# mainboard.net
KiCad netlist of a schematic drawn in EAGLE
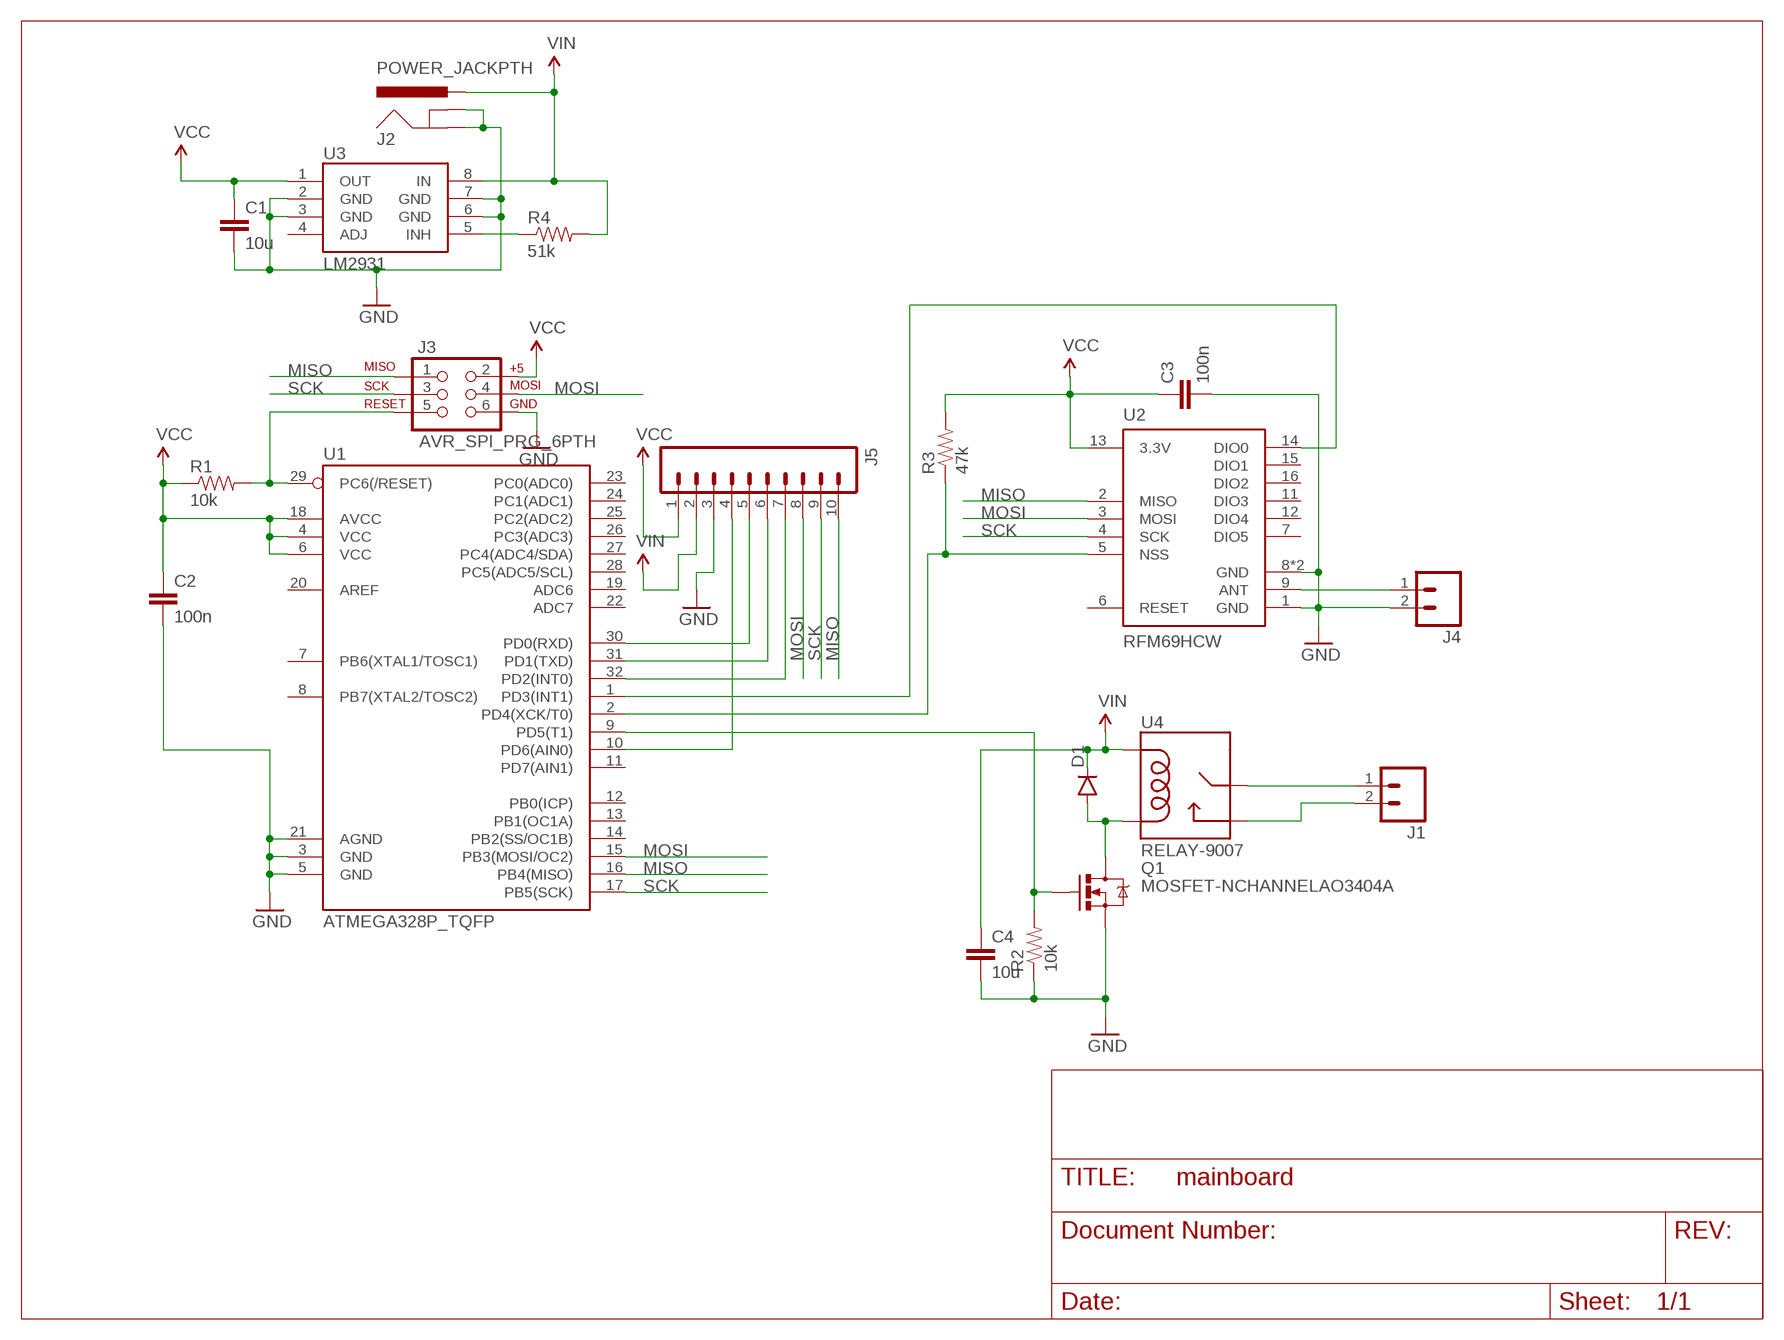
[diagram p0: schematic, sheet 1]

(export (version "E")
  (design (tool "Eeschema 10.0.6"))
  (components
    (comp (ref "C1")
      (value "10u")
      (footprint "eagle-import:1206")
      (libsource (lib "eagle-import") (part "CAP1206"))
    )
    (comp (ref "C2")
      (value "100n")
      (footprint "eagle-import:0603-CAP")
      (libsource (lib "eagle-import") (part "CAP0603-CAP"))
    )
    (comp (ref "C3")
      (value "100n")
      (footprint "eagle-import:0603-CAP")
      (libsource (lib "eagle-import") (part "CAP0603-CAP"))
    )
    (comp (ref "C4")
      (value "10u")
      (footprint "eagle-import:1206")
      (libsource (lib "eagle-import") (part "CAP1206"))
    )
    (comp (ref "D1")
      (value "DIODEBAS16")
      (footprint "eagle-import:SOD-323")
      (libsource (lib "eagle-import") (part "DIODEBAS16"))
    )
    (comp (ref "J1")
      (value "M025MM")
      (footprint "eagle-import:SCREWTERMINAL-5MM-2")
      (libsource (lib "eagle-import") (part "M025MM"))
    )
    (comp (ref "J2")
      (value "POWER_JACKPTH")
      (footprint "eagle-import:POWER_JACK_PTH")
      (libsource (lib "eagle-import") (part "POWER_JACKPTH"))
    )
    (comp (ref "J3")
      (value "AVR_SPI_PRG_6PTH")
      (footprint "eagle-import:2X3")
      (libsource (lib "eagle-import") (part "AVR_SPI_PRG_6PTH"))
    )
    (comp (ref "J4")
      (value "M02PTH")
      (footprint "eagle-import:1X02")
      (libsource (lib "eagle-import") (part "M02PTH"))
    )
    (comp (ref "J5")
      (value "M10SILK_FEMALE_PTH")
      (footprint "eagle-import:1X10")
      (libsource (lib "eagle-import") (part "M10SILK_FEMALE_PTH"))
    )
    (comp (ref "Q1")
      (value "MOSFET-NCHANNELAO3404A")
      (footprint "eagle-import:SOT23-3")
      (libsource (lib "eagle-import") (part "MOSFET-NCHANNELAO3404A"))
    )
    (comp (ref "R1")
      (value "10k")
      (footprint "eagle-import:0603-RES")
      (libsource (lib "eagle-import") (part "RESISTOR0603-RES"))
    )
    (comp (ref "R2")
      (value "10k")
      (footprint "eagle-import:0603-RES")
      (libsource (lib "eagle-import") (part "RESISTOR0603-RES"))
    )
    (comp (ref "R3")
      (value "47k")
      (footprint "eagle-import:0603-RES")
      (libsource (lib "eagle-import") (part "RESISTOR0603-RES"))
    )
    (comp (ref "R4")
      (value "51k")
      (footprint "eagle-import:0603-RES")
      (libsource (lib "eagle-import") (part "RESISTOR0603-RES"))
    )
    (comp (ref "U1")
      (value "ATMEGA328P_TQFP")
      (footprint "eagle-import:TQFP32-08")
      (libsource (lib "eagle-import") (part "ATMEGA328P_TQFP"))
    )
    (comp (ref "U2")
      (value "RFM69HCW")
      (footprint "eagle-import:RFM69HCW-XXXS2")
      (libsource (lib "eagle-import") (part "RFM69HCW"))
    )
    (comp (ref "U3")
      (value "LM2931")
      (footprint "eagle-import:SO08")
      (libsource (lib "eagle-import") (part "LM2931"))
    )
    (comp (ref "U4")
      (value "RELAY-9007")
      (footprint "eagle-import:RELAY-9007")
      (libsource (lib "eagle-import") (part "RELAY-9007"))
    )
  )
  (nets
    (net (code "1") (name "/MISO") (class "Default")
      (node (ref "J3") (pin "1") (pinfunction "1_1") (pintype "passive"))
      (node (ref "J5") (pin "10") (pinfunction "10_10") (pintype "passive"))
      (node (ref "U1") (pin "16") (pinfunction "PB4(MISO)_16") (pintype "bidirectional"))
      (node (ref "U2") (pin "2") (pinfunction "MISO_2") (pintype "bidirectional"))
    )
    (net (code "2") (name "/MOSI") (class "Default")
      (node (ref "J3") (pin "4") (pinfunction "4_4") (pintype "passive"))
      (node (ref "J5") (pin "8") (pinfunction "8_8") (pintype "passive"))
      (node (ref "U1") (pin "15") (pinfunction "PB3(MOSI/OC2)_15") (pintype "bidirectional"))
      (node (ref "U2") (pin "3") (pinfunction "MOSI_3") (pintype "input"))
    )
    (net (code "3") (name "/SCK") (class "Default")
      (node (ref "J3") (pin "3") (pinfunction "3_3") (pintype "passive"))
      (node (ref "J5") (pin "9") (pinfunction "9_9") (pintype "passive"))
      (node (ref "U1") (pin "17") (pinfunction "PB5(SCK)_17") (pintype "bidirectional"))
      (node (ref "U2") (pin "4") (pinfunction "SCK_4") (pintype "input"))
    )
    (net (code "4") (name "GND") (class "Default")
      (node (ref "C1") (pin "2") (pinfunction "2_2") (pintype "passive"))
      (node (ref "C2") (pin "2") (pinfunction "2_2") (pintype "passive"))
      (node (ref "C3") (pin "2") (pinfunction "2_2") (pintype "passive"))
      (node (ref "C4") (pin "2") (pinfunction "2_2") (pintype "passive"))
      (node (ref "J2") (pin "GND") (pinfunction "GND_GND") (pintype "bidirectional"))
      (node (ref "J2") (pin "GNDBREAK") (pinfunction "GNDBREAK_GNDBREAK") (pintype "bidirectional"))
      (node (ref "J3") (pin "6") (pinfunction "6_6") (pintype "passive"))
      (node (ref "J4") (pin "2") (pinfunction "2_2") (pintype "passive"))
      (node (ref "J5") (pin "3") (pinfunction "3_3") (pintype "passive"))
      (node (ref "Q1") (pin "2") (pinfunction "S_2") (pintype "passive"))
      (node (ref "R2") (pin "1") (pinfunction "1_1") (pintype "passive"))
      (node (ref "U1") (pin "21") (pinfunction "AGND_21") (pintype "bidirectional"))
      (node (ref "U1") (pin "3") (pinfunction "GND_3") (pintype "bidirectional"))
      (node (ref "U1") (pin "5") (pinfunction "GND_5") (pintype "bidirectional"))
      (node (ref "U2") (pin "1") (pinfunction "GND_1") (pintype "power_in"))
      (node (ref "U2") (pin "10") (pinfunction "GND_10") (pintype "power_in"))
      (node (ref "U2") (pin "8") (pinfunction "GND_8") (pintype "power_in"))
      (node (ref "U3") (pin "2") (pinfunction "GND_2") (pintype "bidirectional"))
      (node (ref "U3") (pin "3") (pinfunction "GND_3") (pintype "bidirectional"))
      (node (ref "U3") (pin "6") (pinfunction "GND_6") (pintype "bidirectional"))
      (node (ref "U3") (pin "7") (pinfunction "GND_7") (pintype "bidirectional"))
    )
    (net (code "5") (name "Net-(Q1-D)") (class "Default")
      (node (ref "D1") (pin "A") (pinfunction "A_A") (pintype "passive"))
      (node (ref "Q1") (pin "3") (pinfunction "D_3") (pintype "passive"))
      (node (ref "U4") (pin "3") (pinfunction "COIL2_3") (pintype "bidirectional"))
    )
    (net (code "6") (name "Net-(Q1-G)") (class "Default")
      (node (ref "Q1") (pin "1") (pinfunction "G_1") (pintype "passive"))
      (node (ref "R2") (pin "2") (pinfunction "2_2") (pintype "passive"))
      (node (ref "U1") (pin "9") (pinfunction "PD5(T1)_9") (pintype "bidirectional"))
    )
    (net (code "7") (name "Net-(U1-PC6({slash}RESET))") (class "Default")
      (node (ref "J3") (pin "5") (pinfunction "5_5") (pintype "passive"))
      (node (ref "R1") (pin "2") (pinfunction "2_2") (pintype "passive"))
      (node (ref "U1") (pin "29") (pinfunction "PC6(/RESET)_29") (pintype "bidirectional"))
    )
    (net (code "8") (name "Net-(U1-PD0(RXD))") (class "Default")
      (node (ref "J5") (pin "5") (pinfunction "5_5") (pintype "passive"))
      (node (ref "U1") (pin "30") (pinfunction "PD0(RXD)_30") (pintype "bidirectional"))
    )
    (net (code "9") (name "Net-(U1-PD1(TXD))") (class "Default")
      (node (ref "J5") (pin "6") (pinfunction "6_6") (pintype "passive"))
      (node (ref "U1") (pin "31") (pinfunction "PD1(TXD)_31") (pintype "bidirectional"))
    )
    (net (code "10") (name "Net-(U1-PD2(INT0))") (class "Default")
      (node (ref "J5") (pin "7") (pinfunction "7_7") (pintype "passive"))
      (node (ref "U1") (pin "32") (pinfunction "PD2(INT0)_32") (pintype "bidirectional"))
    )
    (net (code "11") (name "Net-(U1-PD3(INT1))") (class "Default")
      (node (ref "U1") (pin "1") (pinfunction "PD3(INT1)_1") (pintype "bidirectional"))
      (node (ref "U2") (pin "14") (pinfunction "DIO0_14") (pintype "bidirectional"))
    )
    (net (code "12") (name "Net-(U1-PD4(XCK{slash}T0))") (class "Default")
      (node (ref "R3") (pin "1") (pinfunction "1_1") (pintype "passive"))
      (node (ref "U1") (pin "2") (pinfunction "PD4(XCK/T0)_2") (pintype "bidirectional"))
      (node (ref "U2") (pin "5") (pinfunction "NSS_5") (pintype "input"))
    )
    (net (code "13") (name "Net-(U1-PD6(AIN0))") (class "Default")
      (node (ref "J5") (pin "4") (pinfunction "4_4") (pintype "passive"))
      (node (ref "U1") (pin "10") (pinfunction "PD6(AIN0)_10") (pintype "bidirectional"))
    )
    (net (code "14") (name "Net-(U2-ANT)") (class "Default")
      (node (ref "J4") (pin "1") (pinfunction "1_1") (pintype "passive"))
      (node (ref "U2") (pin "9") (pinfunction "ANT_9") (pintype "passive"))
    )
    (net (code "15") (name "Net-(U3-INH)") (class "Default")
      (node (ref "R4") (pin "1") (pinfunction "1_1") (pintype "passive"))
      (node (ref "U3") (pin "5") (pinfunction "INH_5") (pintype "bidirectional"))
    )
    (net (code "16") (name "Net-(U4-MAIN)") (class "Default")
      (node (ref "J1") (pin "1") (pinfunction "1_1") (pintype "passive"))
      (node (ref "U4") (pin "1") (pinfunction "MAIN_1") (pintype "bidirectional"))
    )
    (net (code "17") (name "Net-(U4-NO)") (class "Default")
      (node (ref "J1") (pin "2") (pinfunction "2_2") (pintype "passive"))
      (node (ref "U4") (pin "4") (pinfunction "NO_4") (pintype "bidirectional"))
    )
    (net (code "18") (name "VCC") (class "Default")
      (node (ref "C1") (pin "1") (pinfunction "1_1") (pintype "passive"))
      (node (ref "C2") (pin "1") (pinfunction "1_1") (pintype "passive"))
      (node (ref "C3") (pin "1") (pinfunction "1_1") (pintype "passive"))
      (node (ref "J3") (pin "2") (pinfunction "2_2") (pintype "passive"))
      (node (ref "J5") (pin "1") (pinfunction "1_1") (pintype "passive"))
      (node (ref "R1") (pin "1") (pinfunction "1_1") (pintype "passive"))
      (node (ref "R3") (pin "2") (pinfunction "2_2") (pintype "passive"))
      (node (ref "U1") (pin "18") (pinfunction "AVCC_18") (pintype "bidirectional"))
      (node (ref "U1") (pin "4") (pinfunction "VCC_4") (pintype "bidirectional"))
      (node (ref "U1") (pin "6") (pinfunction "VCC_6") (pintype "bidirectional"))
      (node (ref "U2") (pin "13") (pinfunction "3.3V_13") (pintype "power_in"))
      (node (ref "U3") (pin "1") (pinfunction "OUT_1") (pintype "bidirectional"))
    )
    (net (code "19") (name "VIN") (class "Default")
      (node (ref "C4") (pin "1") (pinfunction "1_1") (pintype "passive"))
      (node (ref "D1") (pin "C") (pinfunction "C_C") (pintype "passive"))
      (node (ref "J2") (pin "PWR") (pinfunction "PWR_PWR") (pintype "bidirectional"))
      (node (ref "J5") (pin "2") (pinfunction "2_2") (pintype "passive"))
      (node (ref "R4") (pin "2") (pinfunction "2_2") (pintype "passive"))
      (node (ref "U3") (pin "8") (pinfunction "IN_8") (pintype "bidirectional"))
      (node (ref "U4") (pin "2") (pinfunction "COIL1_2") (pintype "bidirectional"))
    )
    (net (code "20") (name "unconnected-(U1-ADC6-Pad19)") (class "Default")
      (node (ref "U1") (pin "19") (pinfunction "ADC6_19") (pintype "bidirectional"))
    )
    (net (code "21") (name "unconnected-(U1-ADC7-Pad22)") (class "Default")
      (node (ref "U1") (pin "22") (pinfunction "ADC7_22") (pintype "bidirectional"))
    )
    (net (code "22") (name "unconnected-(U1-AREF-Pad20)") (class "Default")
      (node (ref "U1") (pin "20") (pinfunction "AREF_20") (pintype "bidirectional"))
    )
    (net (code "23") (name "unconnected-(U1-PB0(ICP)-Pad12)") (class "Default")
      (node (ref "U1") (pin "12") (pinfunction "PB0(ICP)_12") (pintype "bidirectional"))
    )
    (net (code "24") (name "unconnected-(U1-PB1(OC1A)-Pad13)") (class "Default")
      (node (ref "U1") (pin "13") (pinfunction "PB1(OC1A)_13") (pintype "bidirectional"))
    )
    (net (code "25") (name "unconnected-(U1-PB2(SS{slash}OC1B)-Pad14)") (class "Default")
      (node (ref "U1") (pin "14") (pinfunction "PB2(SS/OC1B)_14") (pintype "bidirectional"))
    )
    (net (code "26") (name "unconnected-(U1-PB6(XTAL1{slash}TOSC1)-Pad7)") (class "Default")
      (node (ref "U1") (pin "7") (pinfunction "PB6(XTAL1/TOSC1)_7") (pintype "bidirectional"))
    )
    (net (code "27") (name "unconnected-(U1-PB7(XTAL2{slash}TOSC2)-Pad8)") (class "Default")
      (node (ref "U1") (pin "8") (pinfunction "PB7(XTAL2/TOSC2)_8") (pintype "bidirectional"))
    )
    (net (code "28") (name "unconnected-(U1-PC0(ADC0)-Pad23)") (class "Default")
      (node (ref "U1") (pin "23") (pinfunction "PC0(ADC0)_23") (pintype "bidirectional"))
    )
    (net (code "29") (name "unconnected-(U1-PC1(ADC1)-Pad24)") (class "Default")
      (node (ref "U1") (pin "24") (pinfunction "PC1(ADC1)_24") (pintype "bidirectional"))
    )
    (net (code "30") (name "unconnected-(U1-PC2(ADC2)-Pad25)") (class "Default")
      (node (ref "U1") (pin "25") (pinfunction "PC2(ADC2)_25") (pintype "bidirectional"))
    )
    (net (code "31") (name "unconnected-(U1-PC3(ADC3)-Pad26)") (class "Default")
      (node (ref "U1") (pin "26") (pinfunction "PC3(ADC3)_26") (pintype "bidirectional"))
    )
    (net (code "32") (name "unconnected-(U1-PC4(ADC4{slash}SDA)-Pad27)") (class "Default")
      (node (ref "U1") (pin "27") (pinfunction "PC4(ADC4/SDA)_27") (pintype "bidirectional"))
    )
    (net (code "33") (name "unconnected-(U1-PC5(ADC5{slash}SCL)-Pad28)") (class "Default")
      (node (ref "U1") (pin "28") (pinfunction "PC5(ADC5/SCL)_28") (pintype "bidirectional"))
    )
    (net (code "34") (name "unconnected-(U1-PD7(AIN1)-Pad11)") (class "Default")
      (node (ref "U1") (pin "11") (pinfunction "PD7(AIN1)_11") (pintype "bidirectional"))
    )
    (net (code "35") (name "unconnected-(U2-DIO1-Pad15)") (class "Default")
      (node (ref "U2") (pin "15") (pinfunction "DIO1_15") (pintype "bidirectional"))
    )
    (net (code "36") (name "unconnected-(U2-DIO2-Pad16)") (class "Default")
      (node (ref "U2") (pin "16") (pinfunction "DIO2_16") (pintype "bidirectional"))
    )
    (net (code "37") (name "unconnected-(U2-DIO3-Pad11)") (class "Default")
      (node (ref "U2") (pin "11") (pinfunction "DIO3_11") (pintype "bidirectional"))
    )
    (net (code "38") (name "unconnected-(U2-DIO4-Pad12)") (class "Default")
      (node (ref "U2") (pin "12") (pinfunction "DIO4_12") (pintype "bidirectional"))
    )
    (net (code "39") (name "unconnected-(U2-DIO5-Pad7)") (class "Default")
      (node (ref "U2") (pin "7") (pinfunction "DIO5_7") (pintype "bidirectional"))
    )
    (net (code "40") (name "unconnected-(U2-RESET-Pad6)") (class "Default")
      (node (ref "U2") (pin "6") (pinfunction "RESET_6") (pintype "input"))
    )
    (net (code "41") (name "unconnected-(U3-ADJ-Pad4)") (class "Default")
      (node (ref "U3") (pin "4") (pinfunction "ADJ_4") (pintype "bidirectional"))
    )
  )
)
